# labwiz-module_t420-0_2.net
KiCad netlist of a schematic drawn in EAGLE
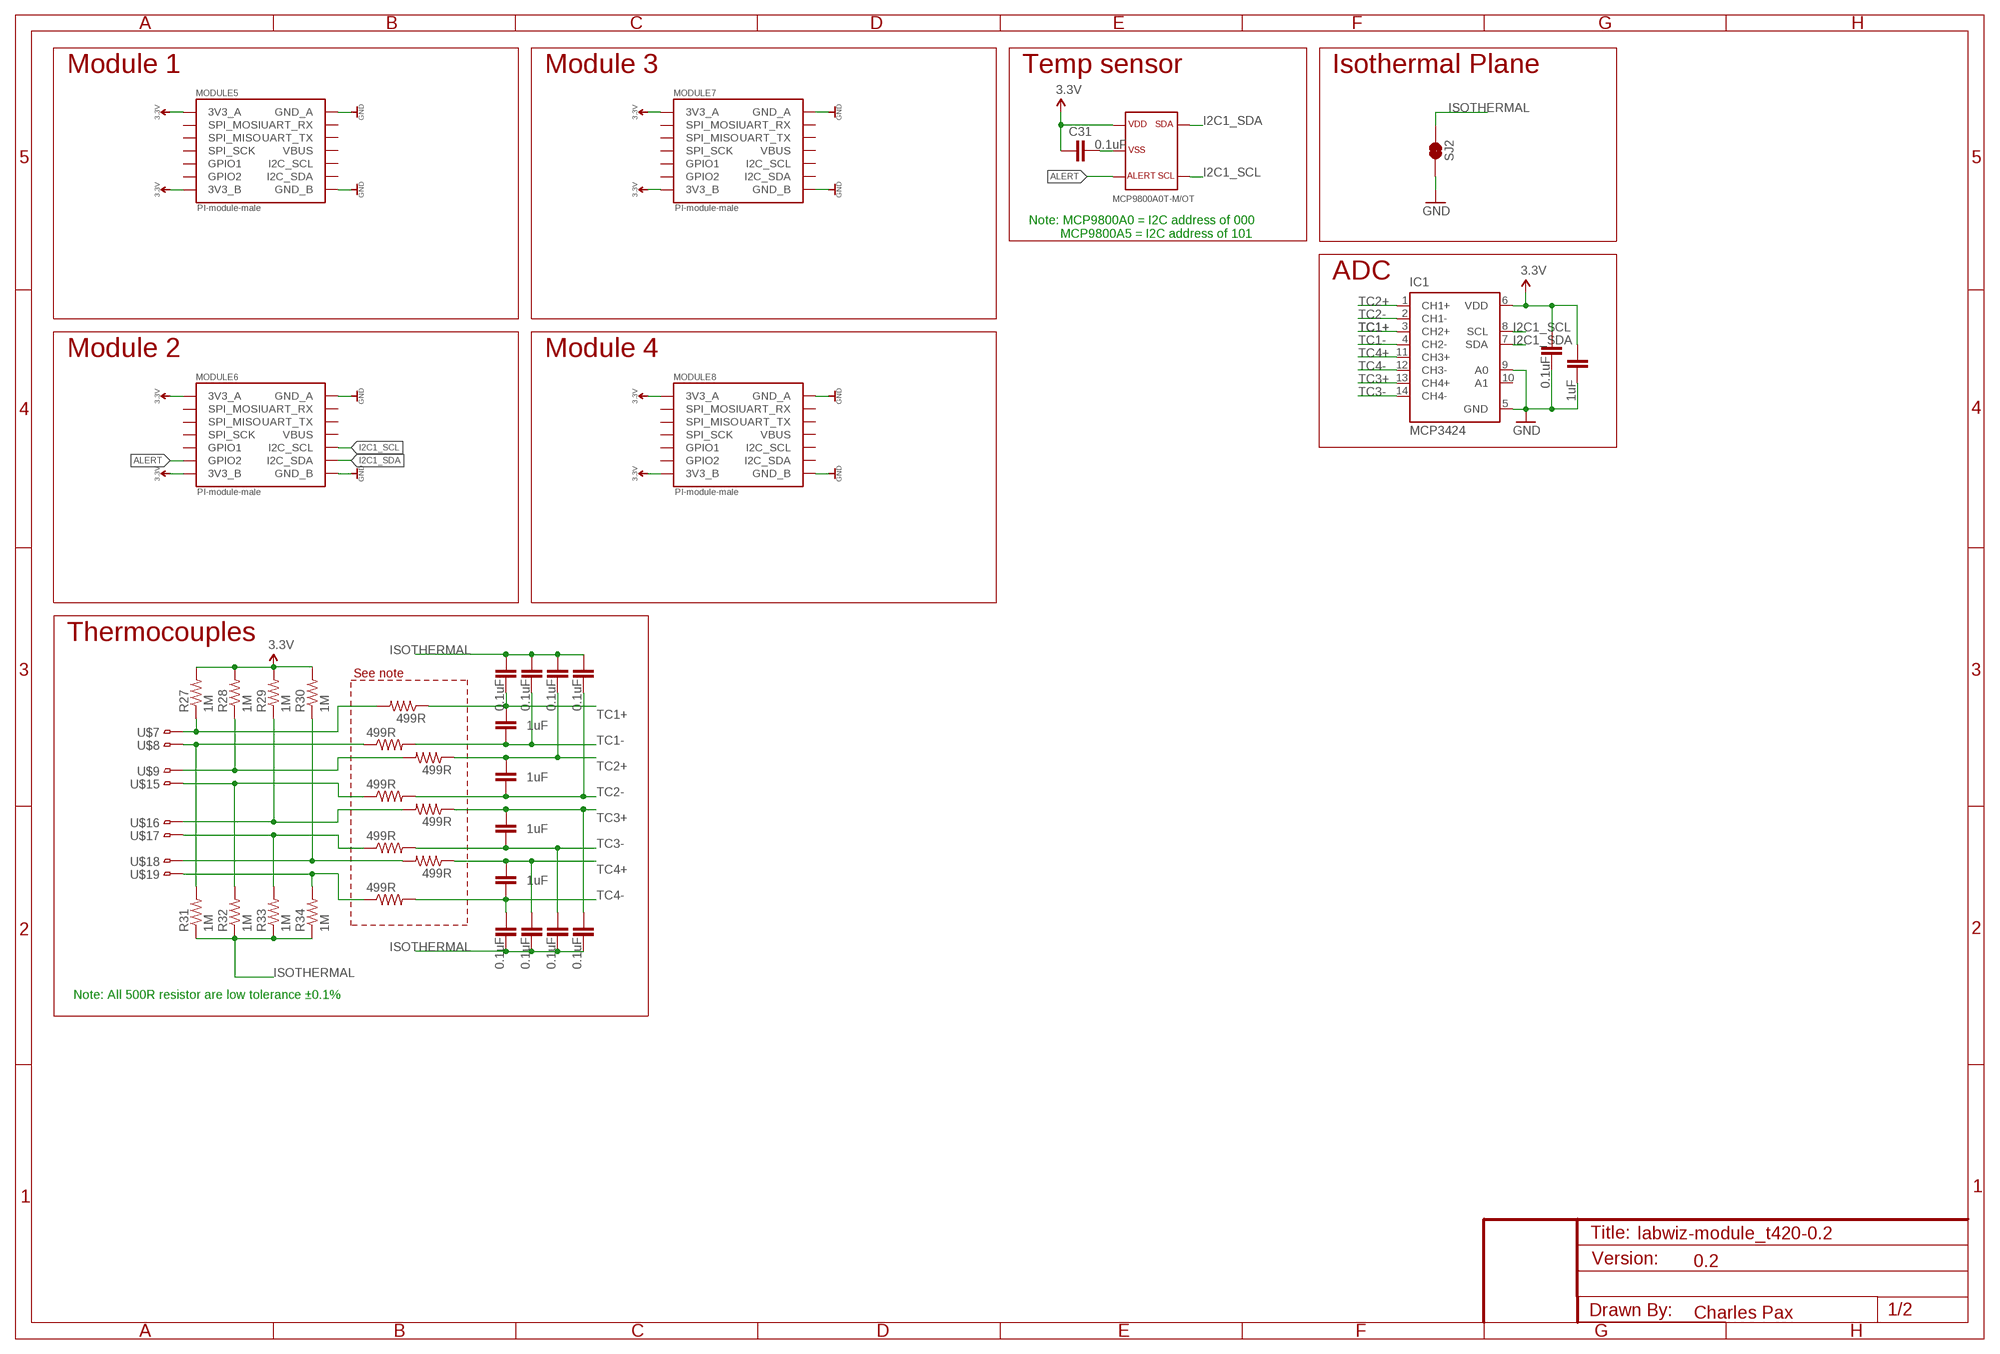
[diagram p0: schematic, sheet 1]

(export (version "E")
  (design (tool "Eeschema 10.0.6"))
  (components
    (comp (ref "C7")
      (value "1uF")
      (footprint "eagle-import:SPARKFUN-CAPACITORS_0603-CAP")
      (libsource (lib "eagle-import") (part "SPARKFUN-CAPACITORS_CAP0603-CAP"))
    )
    (comp (ref "C8")
      (value "1uF")
      (footprint "eagle-import:SPARKFUN-CAPACITORS_0603-CAP")
      (libsource (lib "eagle-import") (part "SPARKFUN-CAPACITORS_CAP0603-CAP"))
    )
    (comp (ref "C10")
      (value "1uF")
      (footprint "eagle-import:SPARKFUN-CAPACITORS_0603-CAP")
      (libsource (lib "eagle-import") (part "SPARKFUN-CAPACITORS_CAP0603-CAP"))
    )
    (comp (ref "C11")
      (value "1uF")
      (footprint "eagle-import:SPARKFUN-CAPACITORS_0603-CAP")
      (libsource (lib "eagle-import") (part "SPARKFUN-CAPACITORS_CAP0603-CAP"))
    )
    (comp (ref "C13")
      (value "0.1uF")
      (footprint "eagle-import:SPARKFUN-CAPACITORS_0603-CAP")
      (libsource (lib "eagle-import") (part "SPARKFUN-CAPACITORS_CAP0603-CAP"))
    )
    (comp (ref "C14")
      (value "0.1uF")
      (footprint "eagle-import:SPARKFUN-CAPACITORS_0603-CAP")
      (libsource (lib "eagle-import") (part "SPARKFUN-CAPACITORS_CAP0603-CAP"))
    )
    (comp (ref "C15")
      (value "0.1uF")
      (footprint "eagle-import:SPARKFUN-CAPACITORS_0603-CAP")
      (libsource (lib "eagle-import") (part "SPARKFUN-CAPACITORS_CAP0603-CAP"))
    )
    (comp (ref "C16")
      (value "0.1uF")
      (footprint "eagle-import:SPARKFUN-CAPACITORS_0603-CAP")
      (libsource (lib "eagle-import") (part "SPARKFUN-CAPACITORS_CAP0603-CAP"))
    )
    (comp (ref "C17")
      (value "0.1uF")
      (footprint "eagle-import:SPARKFUN-CAPACITORS_0603-CAP")
      (libsource (lib "eagle-import") (part "SPARKFUN-CAPACITORS_CAP0603-CAP"))
    )
    (comp (ref "C24")
      (value "0.1uF")
      (footprint "eagle-import:SPARKFUN-CAPACITORS_0603-CAP")
      (libsource (lib "eagle-import") (part "SPARKFUN-CAPACITORS_CAP0603-CAP"))
    )
    (comp (ref "C25")
      (value "0.1uF")
      (footprint "eagle-import:SPARKFUN-CAPACITORS_0603-CAP")
      (libsource (lib "eagle-import") (part "SPARKFUN-CAPACITORS_CAP0603-CAP"))
    )
    (comp (ref "C29")
      (value "0.1uF")
      (footprint "eagle-import:SPARKFUN-CAPACITORS_0603-CAP")
      (libsource (lib "eagle-import") (part "SPARKFUN-CAPACITORS_CAP0603-CAP"))
    )
    (comp (ref "C30")
      (value "1uF")
      (footprint "eagle-import:SPARKFUN-CAPACITORS_0603-CAP")
      (libsource (lib "eagle-import") (part "SPARKFUN-CAPACITORS_CAP0603-CAP"))
    )
    (comp (ref "C31")
      (value "0.1uF")
      (footprint "eagle-import:SPARKFUN-CAPACITORS_0603-CAP")
      (libsource (lib "eagle-import") (part "SPARKFUN-CAPACITORS_CAP0603-CAP"))
    )
    (comp (ref "C37")
      (value "0.1uF")
      (footprint "eagle-import:SPARKFUN-CAPACITORS_0603-CAP")
      (libsource (lib "eagle-import") (part "SPARKFUN-CAPACITORS_CAP0603-CAP"))
    )
    (comp (ref "IC1")
      (value "MCP3424")
      (footprint "eagle-import:SO14")
      (fields (field (name "MF") "Microchip Technology") (field (name "MPN") "MCP3424-E/SL"))
      (libsource (lib "eagle-import") (part "MCP3424"))
    )
    (comp (ref "MODULE5")
      (value "PI-module-male")
      (footprint "eagle-import:M07X2_2MM_EDGE")
      (fields (field (name "MF") "Pax Instruments") (field (name "MPN") "PIxxxx"))
      (libsource (lib "eagle-import") (part "PAX_MODULE_EDGE_MALE_MODULE"))
    )
    (comp (ref "MODULE6")
      (value "PI-module-male")
      (footprint "eagle-import:M07X2_2MM_EDGE")
      (fields (field (name "MF") "Pax Instruments") (field (name "MPN") "PIxxxx"))
      (libsource (lib "eagle-import") (part "PAX_MODULE_EDGE_MALE_MODULE"))
    )
    (comp (ref "MODULE7")
      (value "PI-module-male")
      (footprint "eagle-import:M07X2_2MM_EDGE")
      (fields (field (name "MF") "Pax Instruments") (field (name "MPN") "PIxxxx"))
      (libsource (lib "eagle-import") (part "PAX_MODULE_EDGE_MALE_MODULE"))
    )
    (comp (ref "MODULE8")
      (value "PI-module-male")
      (footprint "eagle-import:M07X2_2MM_EDGE")
      (fields (field (name "MF") "Pax Instruments") (field (name "MPN") "PIxxxx"))
      (libsource (lib "eagle-import") (part "PAX_MODULE_EDGE_MALE_MODULE"))
    )
    (comp (ref "R27")
      (value "1M")
      (footprint "eagle-import:SPARKFUN-RESISTORS_0603-RES")
      (libsource (lib "eagle-import") (part "SPARKFUN-RESISTORS_RESISTOR0603-RES"))
    )
    (comp (ref "R28")
      (value "1M")
      (footprint "eagle-import:SPARKFUN-RESISTORS_0603-RES")
      (libsource (lib "eagle-import") (part "SPARKFUN-RESISTORS_RESISTOR0603-RES"))
    )
    (comp (ref "R29")
      (value "1M")
      (footprint "eagle-import:SPARKFUN-RESISTORS_0603-RES")
      (libsource (lib "eagle-import") (part "SPARKFUN-RESISTORS_RESISTOR0603-RES"))
    )
    (comp (ref "R30")
      (value "1M")
      (footprint "eagle-import:SPARKFUN-RESISTORS_0603-RES")
      (libsource (lib "eagle-import") (part "SPARKFUN-RESISTORS_RESISTOR0603-RES"))
    )
    (comp (ref "R31")
      (value "1M")
      (footprint "eagle-import:SPARKFUN-RESISTORS_0603-RES")
      (libsource (lib "eagle-import") (part "SPARKFUN-RESISTORS_RESISTOR0603-RES"))
    )
    (comp (ref "R32")
      (value "1M")
      (footprint "eagle-import:SPARKFUN-RESISTORS_0603-RES")
      (libsource (lib "eagle-import") (part "SPARKFUN-RESISTORS_RESISTOR0603-RES"))
    )
    (comp (ref "R33")
      (value "1M")
      (footprint "eagle-import:SPARKFUN-RESISTORS_0603-RES")
      (libsource (lib "eagle-import") (part "SPARKFUN-RESISTORS_RESISTOR0603-RES"))
    )
    (comp (ref "R34")
      (value "1M")
      (footprint "eagle-import:SPARKFUN-RESISTORS_0603-RES")
      (libsource (lib "eagle-import") (part "SPARKFUN-RESISTORS_RESISTOR0603-RES"))
    )
    (comp (ref "R35")
      (value "499R")
      (footprint "eagle-import:SPARKFUN-RESISTORS_0603-RES")
      (fields (field (name "MF") "Vishay") (field (name "MPN") "TNPW0603499RBEEA"))
      (libsource (lib "eagle-import") (part "SPARKFUN-RESISTORS_RESISTOR0603-RES"))
    )
    (comp (ref "R36")
      (value "499R")
      (footprint "eagle-import:SPARKFUN-RESISTORS_0603-RES")
      (fields (field (name "MF") "Vishay") (field (name "MPN") "TNPW0603499RBEEA"))
      (libsource (lib "eagle-import") (part "SPARKFUN-RESISTORS_RESISTOR0603-RES"))
    )
    (comp (ref "R37")
      (value "499R")
      (footprint "eagle-import:SPARKFUN-RESISTORS_0603-RES")
      (fields (field (name "MF") "Vishay") (field (name "MPN") "TNPW0603499RBEEA"))
      (libsource (lib "eagle-import") (part "SPARKFUN-RESISTORS_RESISTOR0603-RES"))
    )
    (comp (ref "R38")
      (value "499R")
      (footprint "eagle-import:SPARKFUN-RESISTORS_0603-RES")
      (fields (field (name "MF") "Vishay") (field (name "MPN") "TNPW0603499RBEEA"))
      (libsource (lib "eagle-import") (part "SPARKFUN-RESISTORS_RESISTOR0603-RES"))
    )
    (comp (ref "R39")
      (value "499R")
      (footprint "eagle-import:SPARKFUN-RESISTORS_0603-RES")
      (fields (field (name "MF") "Vishay") (field (name "MPN") "TNPW0603499RBEEA"))
      (libsource (lib "eagle-import") (part "SPARKFUN-RESISTORS_RESISTOR0603-RES"))
    )
    (comp (ref "R40")
      (value "499R")
      (footprint "eagle-import:SPARKFUN-RESISTORS_0603-RES")
      (fields (field (name "MF") "Vishay") (field (name "MPN") "TNPW0603499RBEEA"))
      (libsource (lib "eagle-import") (part "SPARKFUN-RESISTORS_RESISTOR0603-RES"))
    )
    (comp (ref "R41")
      (value "499R")
      (footprint "eagle-import:SPARKFUN-RESISTORS_0603-RES")
      (fields (field (name "MF") "Vishay") (field (name "MPN") "TNPW0603499RBEEA"))
      (libsource (lib "eagle-import") (part "SPARKFUN-RESISTORS_RESISTOR0603-RES"))
    )
    (comp (ref "R42")
      (value "499R")
      (footprint "eagle-import:SPARKFUN-RESISTORS_0603-RES")
      (fields (field (name "MF") "Vishay") (field (name "MPN") "TNPW0603499RBEEA"))
      (libsource (lib "eagle-import") (part "SPARKFUN-RESISTORS_RESISTOR0603-RES"))
    )
    (comp (ref "SJ2")
      (value "JUMPER-PAD-2-NC_BY_TRACE")
      (footprint "eagle-import:PAD-JUMPER-2-NC_BY_TRACE_YES_SILK")
      (libsource (lib "eagle-import") (part "JUMPER-PAD-2-NC_BY_TRACE"))
    )
    (comp (ref "U$7")
      (value "TC-MINI-SINGLE")
      (footprint "eagle-import:TC-CLIP-SINGLE")
      (fields (field (name "MF") "Pax Instrument") (field (name "MPN") "Thermo-clip2"))
      (libsource (lib "eagle-import") (part "TC-MINI-SINGLE"))
    )
    (comp (ref "U$8")
      (value "TC-MINI-SINGLE")
      (footprint "eagle-import:TC-CLIP-SINGLE")
      (fields (field (name "MF") "Pax Instrument") (field (name "MPN") "Thermo-clip2"))
      (libsource (lib "eagle-import") (part "TC-MINI-SINGLE"))
    )
    (comp (ref "U$9")
      (value "TC-MINI-SINGLE")
      (footprint "eagle-import:TC-CLIP-SINGLE")
      (fields (field (name "MF") "Pax Instrument") (field (name "MPN") "Thermo-clip2"))
      (libsource (lib "eagle-import") (part "TC-MINI-SINGLE"))
    )
    (comp (ref "U$15")
      (value "TC-MINI-SINGLE")
      (footprint "eagle-import:TC-CLIP-SINGLE")
      (fields (field (name "MF") "Pax Instrument") (field (name "MPN") "Thermo-clip2"))
      (libsource (lib "eagle-import") (part "TC-MINI-SINGLE"))
    )
    (comp (ref "U$16")
      (value "TC-MINI-SINGLE")
      (footprint "eagle-import:TC-CLIP-SINGLE")
      (fields (field (name "MF") "Pax Instrument") (field (name "MPN") "Thermo-clip2"))
      (libsource (lib "eagle-import") (part "TC-MINI-SINGLE"))
    )
    (comp (ref "U$17")
      (value "TC-MINI-SINGLE")
      (footprint "eagle-import:TC-CLIP-SINGLE")
      (fields (field (name "MF") "Pax Instrument") (field (name "MPN") "Thermo-clip2"))
      (libsource (lib "eagle-import") (part "TC-MINI-SINGLE"))
    )
    (comp (ref "U$18")
      (value "TC-MINI-SINGLE")
      (footprint "eagle-import:TC-CLIP-SINGLE")
      (fields (field (name "MF") "Pax Instrument") (field (name "MPN") "Thermo-clip2"))
      (libsource (lib "eagle-import") (part "TC-MINI-SINGLE"))
    )
    (comp (ref "U$19")
      (value "TC-MINI-SINGLE")
      (footprint "eagle-import:TC-CLIP-SINGLE")
      (fields (field (name "MF") "Pax Instrument") (field (name "MPN") "Thermo-clip2"))
      (libsource (lib "eagle-import") (part "TC-MINI-SINGLE"))
    )
    (comp (ref "U1")
      (value "MCP9800")
      (footprint "eagle-import:SOT23-5L")
      (fields (field (name "MF") "Microchip Technology") (field (name "MPN") "MCP9800A0T-M/OT"))
      (libsource (lib "eagle-import") (part "MCP9800"))
    )
  )
  (nets
    (net (code "1") (name "3.3V") (class "Default")
      (node (ref "C29") (pin "1") (pinfunction "1_1") (pintype "passive"))
      (node (ref "C30") (pin "1") (pinfunction "1_1") (pintype "passive"))
      (node (ref "C31") (pin "1") (pinfunction "1_1") (pintype "passive"))
      (node (ref "IC1") (pin "6") (pinfunction "VDD_6") (pintype "power_in"))
      (node (ref "MODULE5") (pin "P$1") (pinfunction "3V3_B_P$1") (pintype "bidirectional"))
      (node (ref "MODULE5") (pin "P$13") (pinfunction "3V3_A_P$13") (pintype "power_in"))
      (node (ref "MODULE6") (pin "P$1") (pinfunction "3V3_B_P$1") (pintype "bidirectional"))
      (node (ref "MODULE6") (pin "P$13") (pinfunction "3V3_A_P$13") (pintype "power_in"))
      (node (ref "MODULE7") (pin "P$1") (pinfunction "3V3_B_P$1") (pintype "bidirectional"))
      (node (ref "MODULE7") (pin "P$13") (pinfunction "3V3_A_P$13") (pintype "power_in"))
      (node (ref "MODULE8") (pin "P$1") (pinfunction "3V3_B_P$1") (pintype "bidirectional"))
      (node (ref "MODULE8") (pin "P$13") (pinfunction "3V3_A_P$13") (pintype "power_in"))
      (node (ref "R27") (pin "2") (pinfunction "2_2") (pintype "passive"))
      (node (ref "R28") (pin "2") (pinfunction "2_2") (pintype "passive"))
      (node (ref "R29") (pin "2") (pinfunction "2_2") (pintype "passive"))
      (node (ref "R30") (pin "2") (pinfunction "2_2") (pintype "passive"))
      (node (ref "U1") (pin "1") (pinfunction "1_1") (pintype "bidirectional"))
    )
    (net (code "2") (name "ALERT") (class "Default")
      (node (ref "MODULE6") (pin "P$3") (pinfunction "GPIO2_P$3") (pintype "bidirectional"))
      (node (ref "U1") (pin "3") (pinfunction "3_3") (pintype "bidirectional"))
    )
    (net (code "3") (name "GND") (class "Default")
      (node (ref "C29") (pin "2") (pinfunction "2_2") (pintype "passive"))
      (node (ref "C30") (pin "2") (pinfunction "2_2") (pintype "passive"))
      (node (ref "IC1") (pin "5") (pinfunction "GND_5") (pintype "power_in"))
      (node (ref "IC1") (pin "9") (pinfunction "A0_9") (pintype "input"))
      (node (ref "MODULE5") (pin "P$14") (pinfunction "GND_A_P$14") (pintype "power_in"))
      (node (ref "MODULE5") (pin "P$2") (pinfunction "GND_B_P$2") (pintype "bidirectional"))
      (node (ref "MODULE6") (pin "P$14") (pinfunction "GND_A_P$14") (pintype "power_in"))
      (node (ref "MODULE6") (pin "P$2") (pinfunction "GND_B_P$2") (pintype "bidirectional"))
      (node (ref "MODULE7") (pin "P$14") (pinfunction "GND_A_P$14") (pintype "power_in"))
      (node (ref "MODULE7") (pin "P$2") (pinfunction "GND_B_P$2") (pintype "bidirectional"))
      (node (ref "MODULE8") (pin "P$14") (pinfunction "GND_A_P$14") (pintype "power_in"))
      (node (ref "MODULE8") (pin "P$2") (pinfunction "GND_B_P$2") (pintype "bidirectional"))
      (node (ref "SJ2") (pin "1") (pinfunction "1_1") (pintype "passive"))
    )
    (net (code "4") (name "I2C1_SCL") (class "Default")
      (node (ref "IC1") (pin "8") (pinfunction "SCL_8") (pintype "input"))
      (node (ref "MODULE6") (pin "P$6") (pinfunction "I2C_SCL_P$6") (pintype "bidirectional"))
      (node (ref "U1") (pin "4") (pinfunction "4_4") (pintype "bidirectional"))
    )
    (net (code "5") (name "I2C1_SDA") (class "Default")
      (node (ref "IC1") (pin "7") (pinfunction "SDA_7") (pintype "bidirectional"))
      (node (ref "MODULE6") (pin "P$4") (pinfunction "I2C_SDA_P$4") (pintype "bidirectional"))
      (node (ref "U1") (pin "5") (pinfunction "5_5") (pintype "bidirectional"))
    )
    (net (code "6") (name "ISOTHERMAL") (class "Default")
      (node (ref "C13") (pin "2") (pinfunction "2_2") (pintype "passive"))
      (node (ref "C14") (pin "2") (pinfunction "2_2") (pintype "passive"))
      (node (ref "C15") (pin "2") (pinfunction "2_2") (pintype "passive"))
      (node (ref "C16") (pin "2") (pinfunction "2_2") (pintype "passive"))
      (node (ref "C17") (pin "1") (pinfunction "1_1") (pintype "passive"))
      (node (ref "C24") (pin "1") (pinfunction "1_1") (pintype "passive"))
      (node (ref "C25") (pin "1") (pinfunction "1_1") (pintype "passive"))
      (node (ref "C31") (pin "2") (pinfunction "2_2") (pintype "passive"))
      (node (ref "C37") (pin "1") (pinfunction "1_1") (pintype "passive"))
      (node (ref "R31") (pin "1") (pinfunction "1_1") (pintype "passive"))
      (node (ref "R32") (pin "1") (pinfunction "1_1") (pintype "passive"))
      (node (ref "R33") (pin "1") (pinfunction "1_1") (pintype "passive"))
      (node (ref "R34") (pin "1") (pinfunction "1_1") (pintype "passive"))
      (node (ref "SJ2") (pin "2") (pinfunction "2_2") (pintype "passive"))
      (node (ref "U1") (pin "2") (pinfunction "2_2") (pintype "bidirectional"))
    )
    (net (code "7") (name "Net-(U$7-1)") (class "Default")
      (node (ref "R27") (pin "1") (pinfunction "1_1") (pintype "passive"))
      (node (ref "R35") (pin "2") (pinfunction "2_2") (pintype "passive"))
      (node (ref "U$7") (pin "P$1") (pinfunction "1_P$1") (pintype "passive"))
    )
    (net (code "8") (name "Net-(U$8-1)") (class "Default")
      (node (ref "R31") (pin "2") (pinfunction "2_2") (pintype "passive"))
      (node (ref "R36") (pin "1") (pinfunction "1_1") (pintype "passive"))
      (node (ref "U$8") (pin "P$1") (pinfunction "1_P$1") (pintype "passive"))
    )
    (net (code "9") (name "Net-(U$9-1)") (class "Default")
      (node (ref "R28") (pin "1") (pinfunction "1_1") (pintype "passive"))
      (node (ref "R37") (pin "2") (pinfunction "2_2") (pintype "passive"))
      (node (ref "U$9") (pin "P$1") (pinfunction "1_P$1") (pintype "passive"))
    )
    (net (code "10") (name "Net-(U$15-1)") (class "Default")
      (node (ref "R32") (pin "2") (pinfunction "2_2") (pintype "passive"))
      (node (ref "R38") (pin "1") (pinfunction "1_1") (pintype "passive"))
      (node (ref "U$15") (pin "P$1") (pinfunction "1_P$1") (pintype "passive"))
    )
    (net (code "11") (name "Net-(U$16-1)") (class "Default")
      (node (ref "R29") (pin "1") (pinfunction "1_1") (pintype "passive"))
      (node (ref "R39") (pin "2") (pinfunction "2_2") (pintype "passive"))
      (node (ref "U$16") (pin "P$1") (pinfunction "1_P$1") (pintype "passive"))
    )
    (net (code "12") (name "Net-(U$17-1)") (class "Default")
      (node (ref "R33") (pin "2") (pinfunction "2_2") (pintype "passive"))
      (node (ref "R41") (pin "1") (pinfunction "1_1") (pintype "passive"))
      (node (ref "U$17") (pin "P$1") (pinfunction "1_P$1") (pintype "passive"))
    )
    (net (code "13") (name "Net-(U$18-1)") (class "Default")
      (node (ref "R30") (pin "1") (pinfunction "1_1") (pintype "passive"))
      (node (ref "R40") (pin "2") (pinfunction "2_2") (pintype "passive"))
      (node (ref "U$18") (pin "P$1") (pinfunction "1_P$1") (pintype "passive"))
    )
    (net (code "14") (name "Net-(U$19-1)") (class "Default")
      (node (ref "R34") (pin "2") (pinfunction "2_2") (pintype "passive"))
      (node (ref "R42") (pin "1") (pinfunction "1_1") (pintype "passive"))
      (node (ref "U$19") (pin "P$1") (pinfunction "1_P$1") (pintype "passive"))
    )
    (net (code "15") (name "TC1+") (class "Default")
      (node (ref "C17") (pin "2") (pinfunction "2_2") (pintype "passive"))
      (node (ref "C7") (pin "1") (pinfunction "1_1") (pintype "passive"))
      (node (ref "IC1") (pin "3") (pinfunction "CH2+_3") (pintype "input"))
      (node (ref "R35") (pin "1") (pinfunction "1_1") (pintype "passive"))
    )
    (net (code "16") (name "TC1-") (class "Default")
      (node (ref "C24") (pin "2") (pinfunction "2_2") (pintype "passive"))
      (node (ref "C7") (pin "2") (pinfunction "2_2") (pintype "passive"))
      (node (ref "IC1") (pin "4") (pinfunction "CH2-_4") (pintype "input"))
      (node (ref "R36") (pin "2") (pinfunction "2_2") (pintype "passive"))
    )
    (net (code "17") (name "TC2+") (class "Default")
      (node (ref "C25") (pin "2") (pinfunction "2_2") (pintype "passive"))
      (node (ref "C8") (pin "1") (pinfunction "1_1") (pintype "passive"))
      (node (ref "IC1") (pin "1") (pinfunction "CH1+_1") (pintype "input"))
      (node (ref "R37") (pin "1") (pinfunction "1_1") (pintype "passive"))
    )
    (net (code "18") (name "TC2-") (class "Default")
      (node (ref "C37") (pin "2") (pinfunction "2_2") (pintype "passive"))
      (node (ref "C8") (pin "2") (pinfunction "2_2") (pintype "passive"))
      (node (ref "IC1") (pin "2") (pinfunction "CH1-_2") (pintype "input"))
      (node (ref "R38") (pin "2") (pinfunction "2_2") (pintype "passive"))
    )
    (net (code "19") (name "TC3+") (class "Default")
      (node (ref "C10") (pin "1") (pinfunction "1_1") (pintype "passive"))
      (node (ref "C16") (pin "1") (pinfunction "1_1") (pintype "passive"))
      (node (ref "IC1") (pin "13") (pinfunction "CH4+_13") (pintype "input"))
      (node (ref "R39") (pin "1") (pinfunction "1_1") (pintype "passive"))
    )
    (net (code "20") (name "TC3-") (class "Default")
      (node (ref "C10") (pin "2") (pinfunction "2_2") (pintype "passive"))
      (node (ref "C15") (pin "1") (pinfunction "1_1") (pintype "passive"))
      (node (ref "IC1") (pin "14") (pinfunction "CH4-_14") (pintype "input"))
      (node (ref "R41") (pin "2") (pinfunction "2_2") (pintype "passive"))
    )
    (net (code "21") (name "TC4+") (class "Default")
      (node (ref "C11") (pin "1") (pinfunction "1_1") (pintype "passive"))
      (node (ref "C14") (pin "1") (pinfunction "1_1") (pintype "passive"))
      (node (ref "IC1") (pin "11") (pinfunction "CH3+_11") (pintype "input"))
      (node (ref "R40") (pin "1") (pinfunction "1_1") (pintype "passive"))
    )
    (net (code "22") (name "TC4-") (class "Default")
      (node (ref "C11") (pin "2") (pinfunction "2_2") (pintype "passive"))
      (node (ref "C13") (pin "1") (pinfunction "1_1") (pintype "passive"))
      (node (ref "IC1") (pin "12") (pinfunction "CH3-_12") (pintype "input"))
      (node (ref "R42") (pin "2") (pinfunction "2_2") (pintype "passive"))
    )
    (net (code "23") (name "unconnected-(IC1-A1-Pad10)") (class "Default")
      (node (ref "IC1") (pin "10") (pinfunction "A1_10") (pintype "input"))
    )
    (net (code "24") (name "unconnected-(MODULE5-GPIO1-PadP$5)") (class "Default")
      (node (ref "MODULE5") (pin "P$5") (pinfunction "GPIO1_P$5") (pintype "bidirectional"))
    )
    (net (code "25") (name "unconnected-(MODULE5-GPIO2-PadP$3)") (class "Default")
      (node (ref "MODULE5") (pin "P$3") (pinfunction "GPIO2_P$3") (pintype "bidirectional"))
    )
    (net (code "26") (name "unconnected-(MODULE5-I2C_SCL-PadP$6)") (class "Default")
      (node (ref "MODULE5") (pin "P$6") (pinfunction "I2C_SCL_P$6") (pintype "bidirectional"))
    )
    (net (code "27") (name "unconnected-(MODULE5-I2C_SDA-PadP$4)") (class "Default")
      (node (ref "MODULE5") (pin "P$4") (pinfunction "I2C_SDA_P$4") (pintype "bidirectional"))
    )
    (net (code "28") (name "unconnected-(MODULE5-SPI_MISO-PadP$9)") (class "Default")
      (node (ref "MODULE5") (pin "P$9") (pinfunction "SPI_MISO_P$9") (pintype "bidirectional"))
    )
    (net (code "29") (name "unconnected-(MODULE5-SPI_MOSI-PadP$11)") (class "Default")
      (node (ref "MODULE5") (pin "P$11") (pinfunction "SPI_MOSI_P$11") (pintype "bidirectional"))
    )
    (net (code "30") (name "unconnected-(MODULE5-SPI_SCK-PadP$7)") (class "Default")
      (node (ref "MODULE5") (pin "P$7") (pinfunction "SPI_SCK_P$7") (pintype "bidirectional"))
    )
    (net (code "31") (name "unconnected-(MODULE5-UART_RX-PadP$12)") (class "Default")
      (node (ref "MODULE5") (pin "P$12") (pinfunction "UART_RX_P$12") (pintype "bidirectional"))
    )
    (net (code "32") (name "unconnected-(MODULE5-UART_TX-PadP$10)") (class "Default")
      (node (ref "MODULE5") (pin "P$10") (pinfunction "UART_TX_P$10") (pintype "bidirectional"))
    )
    (net (code "33") (name "unconnected-(MODULE5-VBUS-PadP$8)") (class "Default")
      (node (ref "MODULE5") (pin "P$8") (pinfunction "VBUS_P$8") (pintype "bidirectional"))
    )
    (net (code "34") (name "unconnected-(MODULE6-GPIO1-PadP$5)") (class "Default")
      (node (ref "MODULE6") (pin "P$5") (pinfunction "GPIO1_P$5") (pintype "bidirectional"))
    )
    (net (code "35") (name "unconnected-(MODULE6-SPI_MISO-PadP$9)") (class "Default")
      (node (ref "MODULE6") (pin "P$9") (pinfunction "SPI_MISO_P$9") (pintype "bidirectional"))
    )
    (net (code "36") (name "unconnected-(MODULE6-SPI_MOSI-PadP$11)") (class "Default")
      (node (ref "MODULE6") (pin "P$11") (pinfunction "SPI_MOSI_P$11") (pintype "bidirectional"))
    )
    (net (code "37") (name "unconnected-(MODULE6-SPI_SCK-PadP$7)") (class "Default")
      (node (ref "MODULE6") (pin "P$7") (pinfunction "SPI_SCK_P$7") (pintype "bidirectional"))
    )
    (net (code "38") (name "unconnected-(MODULE6-UART_RX-PadP$12)") (class "Default")
      (node (ref "MODULE6") (pin "P$12") (pinfunction "UART_RX_P$12") (pintype "bidirectional"))
    )
    (net (code "39") (name "unconnected-(MODULE6-UART_TX-PadP$10)") (class "Default")
      (node (ref "MODULE6") (pin "P$10") (pinfunction "UART_TX_P$10") (pintype "bidirectional"))
    )
    (net (code "40") (name "unconnected-(MODULE6-VBUS-PadP$8)") (class "Default")
      (node (ref "MODULE6") (pin "P$8") (pinfunction "VBUS_P$8") (pintype "bidirectional"))
    )
    (net (code "41") (name "unconnected-(MODULE7-GPIO1-PadP$5)") (class "Default")
      (node (ref "MODULE7") (pin "P$5") (pinfunction "GPIO1_P$5") (pintype "bidirectional"))
    )
    (net (code "42") (name "unconnected-(MODULE7-GPIO2-PadP$3)") (class "Default")
      (node (ref "MODULE7") (pin "P$3") (pinfunction "GPIO2_P$3") (pintype "bidirectional"))
    )
    (net (code "43") (name "unconnected-(MODULE7-I2C_SCL-PadP$6)") (class "Default")
      (node (ref "MODULE7") (pin "P$6") (pinfunction "I2C_SCL_P$6") (pintype "bidirectional"))
    )
    (net (code "44") (name "unconnected-(MODULE7-I2C_SDA-PadP$4)") (class "Default")
      (node (ref "MODULE7") (pin "P$4") (pinfunction "I2C_SDA_P$4") (pintype "bidirectional"))
    )
    (net (code "45") (name "unconnected-(MODULE7-SPI_MISO-PadP$9)") (class "Default")
      (node (ref "MODULE7") (pin "P$9") (pinfunction "SPI_MISO_P$9") (pintype "bidirectional"))
    )
    (net (code "46") (name "unconnected-(MODULE7-SPI_MOSI-PadP$11)") (class "Default")
      (node (ref "MODULE7") (pin "P$11") (pinfunction "SPI_MOSI_P$11") (pintype "bidirectional"))
    )
    (net (code "47") (name "unconnected-(MODULE7-SPI_SCK-PadP$7)") (class "Default")
      (node (ref "MODULE7") (pin "P$7") (pinfunction "SPI_SCK_P$7") (pintype "bidirectional"))
    )
    (net (code "48") (name "unconnected-(MODULE7-UART_RX-PadP$12)") (class "Default")
      (node (ref "MODULE7") (pin "P$12") (pinfunction "UART_RX_P$12") (pintype "bidirectional"))
    )
    (net (code "49") (name "unconnected-(MODULE7-UART_TX-PadP$10)") (class "Default")
      (node (ref "MODULE7") (pin "P$10") (pinfunction "UART_TX_P$10") (pintype "bidirectional"))
    )
    (net (code "50") (name "unconnected-(MODULE7-VBUS-PadP$8)") (class "Default")
      (node (ref "MODULE7") (pin "P$8") (pinfunction "VBUS_P$8") (pintype "bidirectional"))
    )
    (net (code "51") (name "unconnected-(MODULE8-GPIO1-PadP$5)") (class "Default")
      (node (ref "MODULE8") (pin "P$5") (pinfunction "GPIO1_P$5") (pintype "bidirectional"))
    )
    (net (code "52") (name "unconnected-(MODULE8-GPIO2-PadP$3)") (class "Default")
      (node (ref "MODULE8") (pin "P$3") (pinfunction "GPIO2_P$3") (pintype "bidirectional"))
    )
    (net (code "53") (name "unconnected-(MODULE8-I2C_SCL-PadP$6)") (class "Default")
      (node (ref "MODULE8") (pin "P$6") (pinfunction "I2C_SCL_P$6") (pintype "bidirectional"))
    )
    (net (code "54") (name "unconnected-(MODULE8-I2C_SDA-PadP$4)") (class "Default")
      (node (ref "MODULE8") (pin "P$4") (pinfunction "I2C_SDA_P$4") (pintype "bidirectional"))
    )
    (net (code "55") (name "unconnected-(MODULE8-SPI_MISO-PadP$9)") (class "Default")
      (node (ref "MODULE8") (pin "P$9") (pinfunction "SPI_MISO_P$9") (pintype "bidirectional"))
    )
    (net (code "56") (name "unconnected-(MODULE8-SPI_MOSI-PadP$11)") (class "Default")
      (node (ref "MODULE8") (pin "P$11") (pinfunction "SPI_MOSI_P$11") (pintype "bidirectional"))
    )
    (net (code "57") (name "unconnected-(MODULE8-SPI_SCK-PadP$7)") (class "Default")
      (node (ref "MODULE8") (pin "P$7") (pinfunction "SPI_SCK_P$7") (pintype "bidirectional"))
    )
    (net (code "58") (name "unconnected-(MODULE8-UART_RX-PadP$12)") (class "Default")
      (node (ref "MODULE8") (pin "P$12") (pinfunction "UART_RX_P$12") (pintype "bidirectional"))
    )
    (net (code "59") (name "unconnected-(MODULE8-UART_TX-PadP$10)") (class "Default")
      (node (ref "MODULE8") (pin "P$10") (pinfunction "UART_TX_P$10") (pintype "bidirectional"))
    )
    (net (code "60") (name "unconnected-(MODULE8-VBUS-PadP$8)") (class "Default")
      (node (ref "MODULE8") (pin "P$8") (pinfunction "VBUS_P$8") (pintype "bidirectional"))
    )
  )
)
